# CAN.net
KiCad netlist of a schematic drawn in Altium Designer
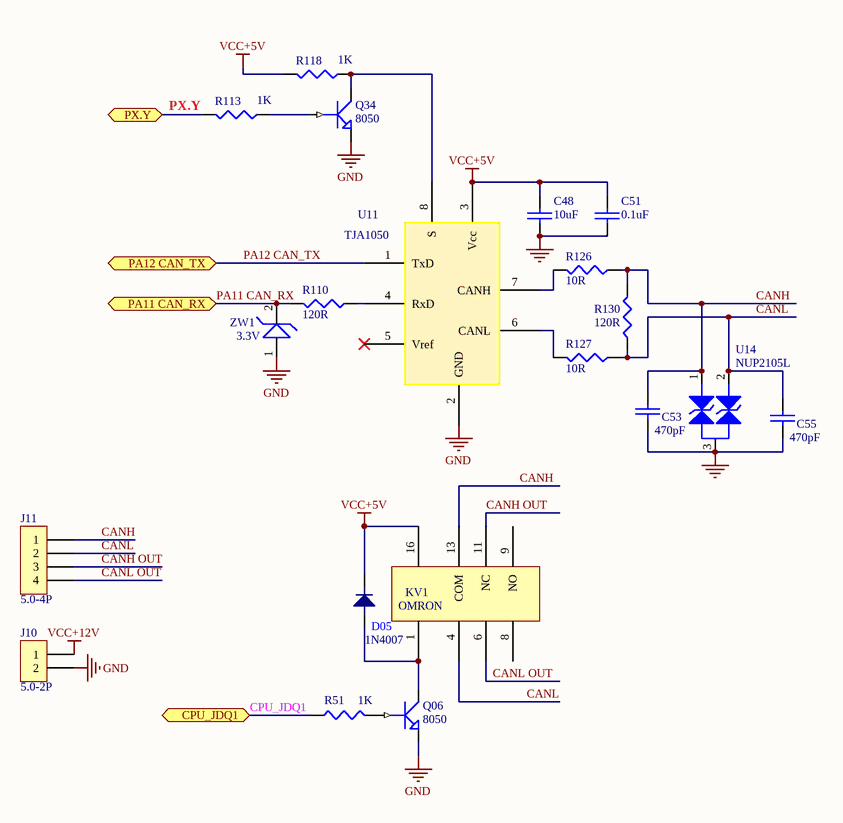
[diagram p0: CAN.SchDoc]

(export (version "E")
  (design (tool "Eeschema 10.0.6"))
  (components
    (comp (ref "C48")
      (value "10uF")
      (footprint "0805")
      (description "0805陶瓷贴片电容")
      (libsource (lib "INSPUR_PCB") (part "CAP-0805"))
    )
    (comp (ref "C51")
      (value "0.1uF")
      (footprint "0603")
      (description "0603陶瓷贴片电容")
      (libsource (lib "INSPUR_PCB") (part "CAP-0603"))
    )
    (comp (ref "C53")
      (value "470pF")
      (footprint "0603")
      (description "0603陶瓷贴片电容")
      (libsource (lib "INSPUR_PCB") (part "CAP-0603"))
    )
    (comp (ref "C55")
      (value "470pF")
      (footprint "0603")
      (description "0603陶瓷贴片电容")
      (libsource (lib "INSPUR_PCB") (part "CAP-0603"))
    )
    (comp (ref "D05")
      (value "1N4007")
      (footprint "DO-214AC(SMA)")
      (description "1A整流二极管")
      (libsource (lib "mylib") (part "1N4007"))
    )
    (comp (ref "J10")
      (value "5.0-2P")
      (footprint "5.0-2")
      (description "WJ301V-5.00-2P")
      (libsource (lib "INSPUR_PCB") (part "5.0-2P"))
    )
    (comp (ref "J11")
      (value "5.0-4P")
      (footprint "5.0-4")
      (description "WJ301V-5.00-4P")
      (libsource (lib "INSPUR_PCB") (part "5.0-4P"))
    )
    (comp (ref "KV1")
      (value "OMRON")
      (footprint "KV")
      (description "omron G5V-2 12VDC")
      (libsource (lib "INSPUR_SCH") (part "OMRON"))
    )
    (comp (ref "Q06") (value "8050") (footprint "SOT-23") (libsource (lib "INSPUR_SCH") (part "NPN1")))
    (comp (ref "Q34")
      (value "8050")
      (footprint "SOT-23")
      (description "8050 NPN型三极管")
      (libsource (lib "INSPUR_PCB") (part "8050"))
    )
    (comp (ref "R51") (value "1K") (footprint "0603") (libsource (lib "INSPUR_SCH") (part "RES1")))
    (comp (ref "R110")
      (value "120R")
      (footprint "0603")
      (description "陶瓷贴片电阻0603封装")
      (libsource (lib "INSPUR_PCB") (part "RES-0603"))
    )
    (comp (ref "R113")
      (value "1K")
      (footprint "0603")
      (description "陶瓷贴片电阻0603封装")
      (libsource (lib "INSPUR_PCB") (part "RES-0603"))
    )
    (comp (ref "R118")
      (value "1K")
      (footprint "0603")
      (description "陶瓷贴片电阻0603封装")
      (libsource (lib "INSPUR_PCB") (part "RES-0603"))
    )
    (comp (ref "R126")
      (value "10R")
      (footprint "0603")
      (description "陶瓷贴片电阻0603封装")
      (libsource (lib "INSPUR_PCB") (part "RES-0603"))
    )
    (comp (ref "R127")
      (value "10R")
      (footprint "0603")
      (description "陶瓷贴片电阻0603封装")
      (libsource (lib "INSPUR_PCB") (part "RES-0603"))
    )
    (comp (ref "R130")
      (value "120R")
      (footprint "0603")
      (description "陶瓷贴片电阻0603封装")
      (libsource (lib "INSPUR_PCB") (part "RES-0603"))
    )
    (comp (ref "U11")
      (value "TJA1050")
      (footprint "SO-8")
      (description "TJA1050   CAN芯片")
      (libsource (lib "INSPUR_PCB") (part "TJA1050"))
    )
    (comp (ref "U14")
      (value "NUP2105L")
      (footprint "SOT-23")
      (description "NUP2105L  TVS三极管")
      (libsource (lib "INSPUR_PCB") (part "NUP2105L"))
    )
    (comp (ref "ZW1")
      (value "3.3V")
      (footprint "LL-34")
      (description "ZMM3V3")
      (libsource (lib "INSPUR_PCB") (part "3.3V"))
    )
  )
  (nets
    (net (code "1") (name "/CANH") (class "Default")
      (node (ref "C53") (pin "2") (pinfunction "2_2") (pintype "passive"))
      (node (ref "J11") (pin "1") (pinfunction "1_1") (pintype "passive"))
      (node (ref "KV1") (pin "13") (pinfunction "COM_13") (pintype "passive"))
      (node (ref "R126") (pin "1") (pinfunction "1_1") (pintype "passive"))
      (node (ref "R130") (pin "2") (pinfunction "2_2") (pintype "passive"))
      (node (ref "U14") (pin "1") (pintype "passive"))
    )
    (net (code "2") (name "/CANH OUT") (class "Default")
      (node (ref "J11") (pin "3") (pinfunction "3_3") (pintype "passive"))
      (node (ref "KV1") (pin "11") (pinfunction "NC_11") (pintype "passive"))
    )
    (net (code "3") (name "/CANL") (class "Default")
      (node (ref "C55") (pin "2") (pinfunction "2_2") (pintype "passive"))
      (node (ref "J11") (pin "2") (pinfunction "2_2") (pintype "passive"))
      (node (ref "KV1") (pin "4") (pinfunction "1_4") (pintype "passive"))
      (node (ref "R127") (pin "1") (pinfunction "1_1") (pintype "passive"))
      (node (ref "R130") (pin "1") (pinfunction "1_1") (pintype "passive"))
      (node (ref "U14") (pin "2") (pinfunction "K_2") (pintype "passive"))
    )
    (net (code "4") (name "/CANL OUT") (class "Default")
      (node (ref "J11") (pin "4") (pinfunction "4_4") (pintype "passive"))
      (node (ref "KV1") (pin "6") (pinfunction "2_6") (pintype "passive"))
    )
    (net (code "5") (name "/CPU_JDQ1") (class "Default")
      (node (ref "R51") (pin "1") (pinfunction "1_1") (pintype "passive"))
    )
    (net (code "6") (name "/PA11 CAN_RX") (class "Default")
      (node (ref "R110") (pin "2") (pinfunction "2_2") (pintype "passive"))
      (node (ref "ZW1") (pin "2") (pintype "passive"))
    )
    (net (code "7") (name "/PA12 CAN_TX") (class "Default")
      (node (ref "U11") (pin "1") (pinfunction "TxD_1") (pintype "passive"))
    )
    (net (code "8") (name "/PX.Y") (class "Default")
      (node (ref "R113") (pin "2") (pinfunction "2_2") (pintype "passive"))
    )
    (net (code "9") (name "GND") (class "Default")
      (node (ref "C48") (pin "2") (pinfunction "2_2") (pintype "passive"))
      (node (ref "C51") (pin "1") (pinfunction "1_1") (pintype "passive"))
      (node (ref "C53") (pin "1") (pinfunction "1_1") (pintype "passive"))
      (node (ref "C55") (pin "1") (pinfunction "1_1") (pintype "passive"))
      (node (ref "J10") (pin "2") (pinfunction "2_2") (pintype "passive"))
      (node (ref "Q06") (pin "2") (pinfunction "E_2") (pintype "passive"))
      (node (ref "Q34") (pin "2") (pinfunction "E_2") (pintype "passive"))
      (node (ref "U11") (pin "2") (pinfunction "GND_2") (pintype "passive"))
      (node (ref "U14") (pin "3") (pintype "passive"))
      (node (ref "ZW1") (pin "1") (pintype "passive"))
    )
    (net (code "10") (name "Net-(Q06-B)") (class "Default")
      (node (ref "Q06") (pin "1") (pinfunction "B_1") (pintype "input"))
      (node (ref "R51") (pin "2") (pinfunction "2_2") (pintype "passive"))
    )
    (net (code "11") (name "Net-(Q06-C)") (class "Default")
      (node (ref "D05") (pin "1") (pintype "passive"))
      (node (ref "KV1") (pin "1") (pintype "passive"))
      (node (ref "Q06") (pin "3") (pinfunction "C_3") (pintype "passive"))
    )
    (net (code "12") (name "Net-(Q34-B)") (class "Default")
      (node (ref "Q34") (pin "1") (pinfunction "B_1") (pintype "input"))
      (node (ref "R113") (pin "1") (pinfunction "1_1") (pintype "passive"))
    )
    (net (code "13") (name "Net-(Q34-C)") (class "Default")
      (node (ref "Q34") (pin "3") (pinfunction "C_3") (pintype "passive"))
      (node (ref "R118") (pin "1") (pinfunction "1_1") (pintype "passive"))
      (node (ref "U11") (pin "8") (pinfunction "S_8") (pintype "passive"))
    )
    (net (code "14") (name "Net-(U11-CANH)") (class "Default")
      (node (ref "R126") (pin "2") (pinfunction "2_2") (pintype "passive"))
      (node (ref "U11") (pin "7") (pinfunction "CANH_7") (pintype "passive"))
    )
    (net (code "15") (name "Net-(U11-CANL)") (class "Default")
      (node (ref "R127") (pin "2") (pinfunction "2_2") (pintype "passive"))
      (node (ref "U11") (pin "6") (pinfunction "CANL_6") (pintype "passive"))
    )
    (net (code "16") (name "Net-(U11-RxD)") (class "Default")
      (node (ref "R110") (pin "1") (pinfunction "1_1") (pintype "passive"))
      (node (ref "U11") (pin "4") (pinfunction "RxD_4") (pintype "passive"))
    )
    (net (code "17") (name "VCC+5V") (class "Default")
      (node (ref "C48") (pin "1") (pinfunction "1_1") (pintype "passive"))
      (node (ref "C51") (pin "2") (pinfunction "2_2") (pintype "passive"))
      (node (ref "D05") (pin "2") (pintype "passive"))
      (node (ref "KV1") (pin "16") (pintype "passive"))
      (node (ref "R118") (pin "2") (pinfunction "2_2") (pintype "passive"))
      (node (ref "U11") (pin "3") (pinfunction "Vcc_3") (pintype "passive"))
    )
    (net (code "18") (name "VCC+12V") (class "Default")
      (node (ref "J10") (pin "1") (pinfunction "1_1") (pintype "passive"))
    )
    (net (code "19") (name "unconnected-(KV1-3-Pad8)") (class "Default")
      (node (ref "KV1") (pin "8") (pinfunction "3_8") (pintype "passive"))
    )
    (net (code "20") (name "unconnected-(KV1-NO-Pad9)") (class "Default")
      (node (ref "KV1") (pin "9") (pinfunction "NO_9") (pintype "passive"))
    )
    (net (code "21") (name "unconnected-(U11-Vref-Pad5)") (class "Default")
      (node (ref "U11") (pin "5") (pinfunction "Vref_5") (pintype "passive+no_connect"))
    )
  )
)
